# slaveMeteo.net
KiCad netlist of a schematic drawn in EAGLE
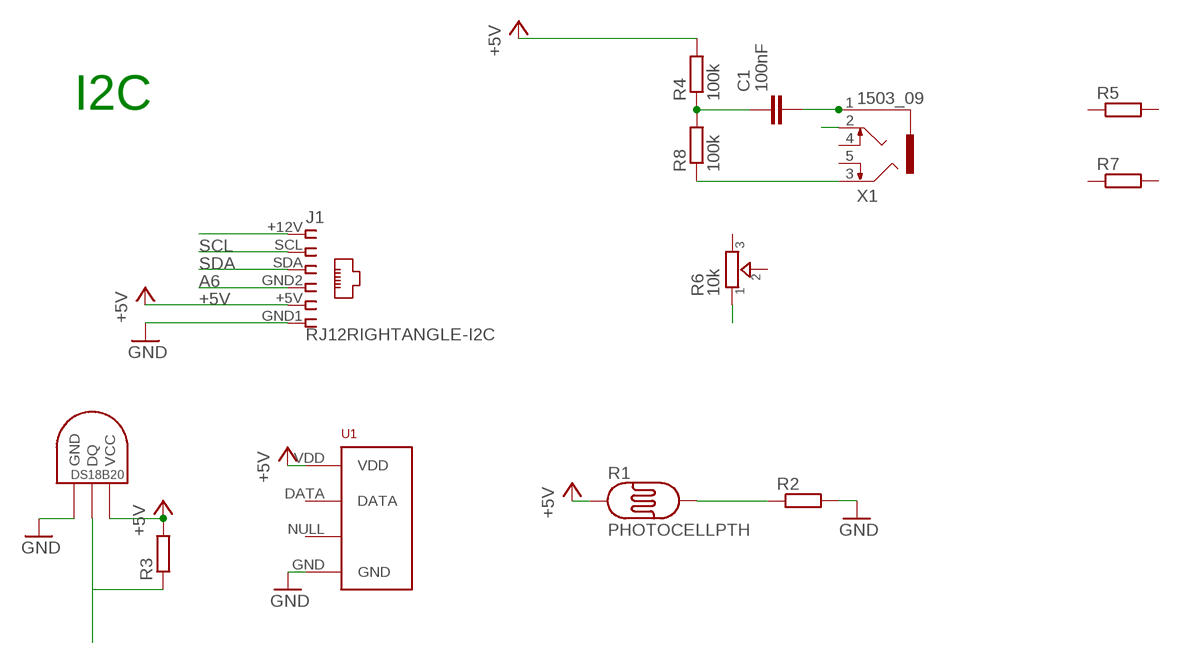
[diagram p0: schematic, sheet 1]
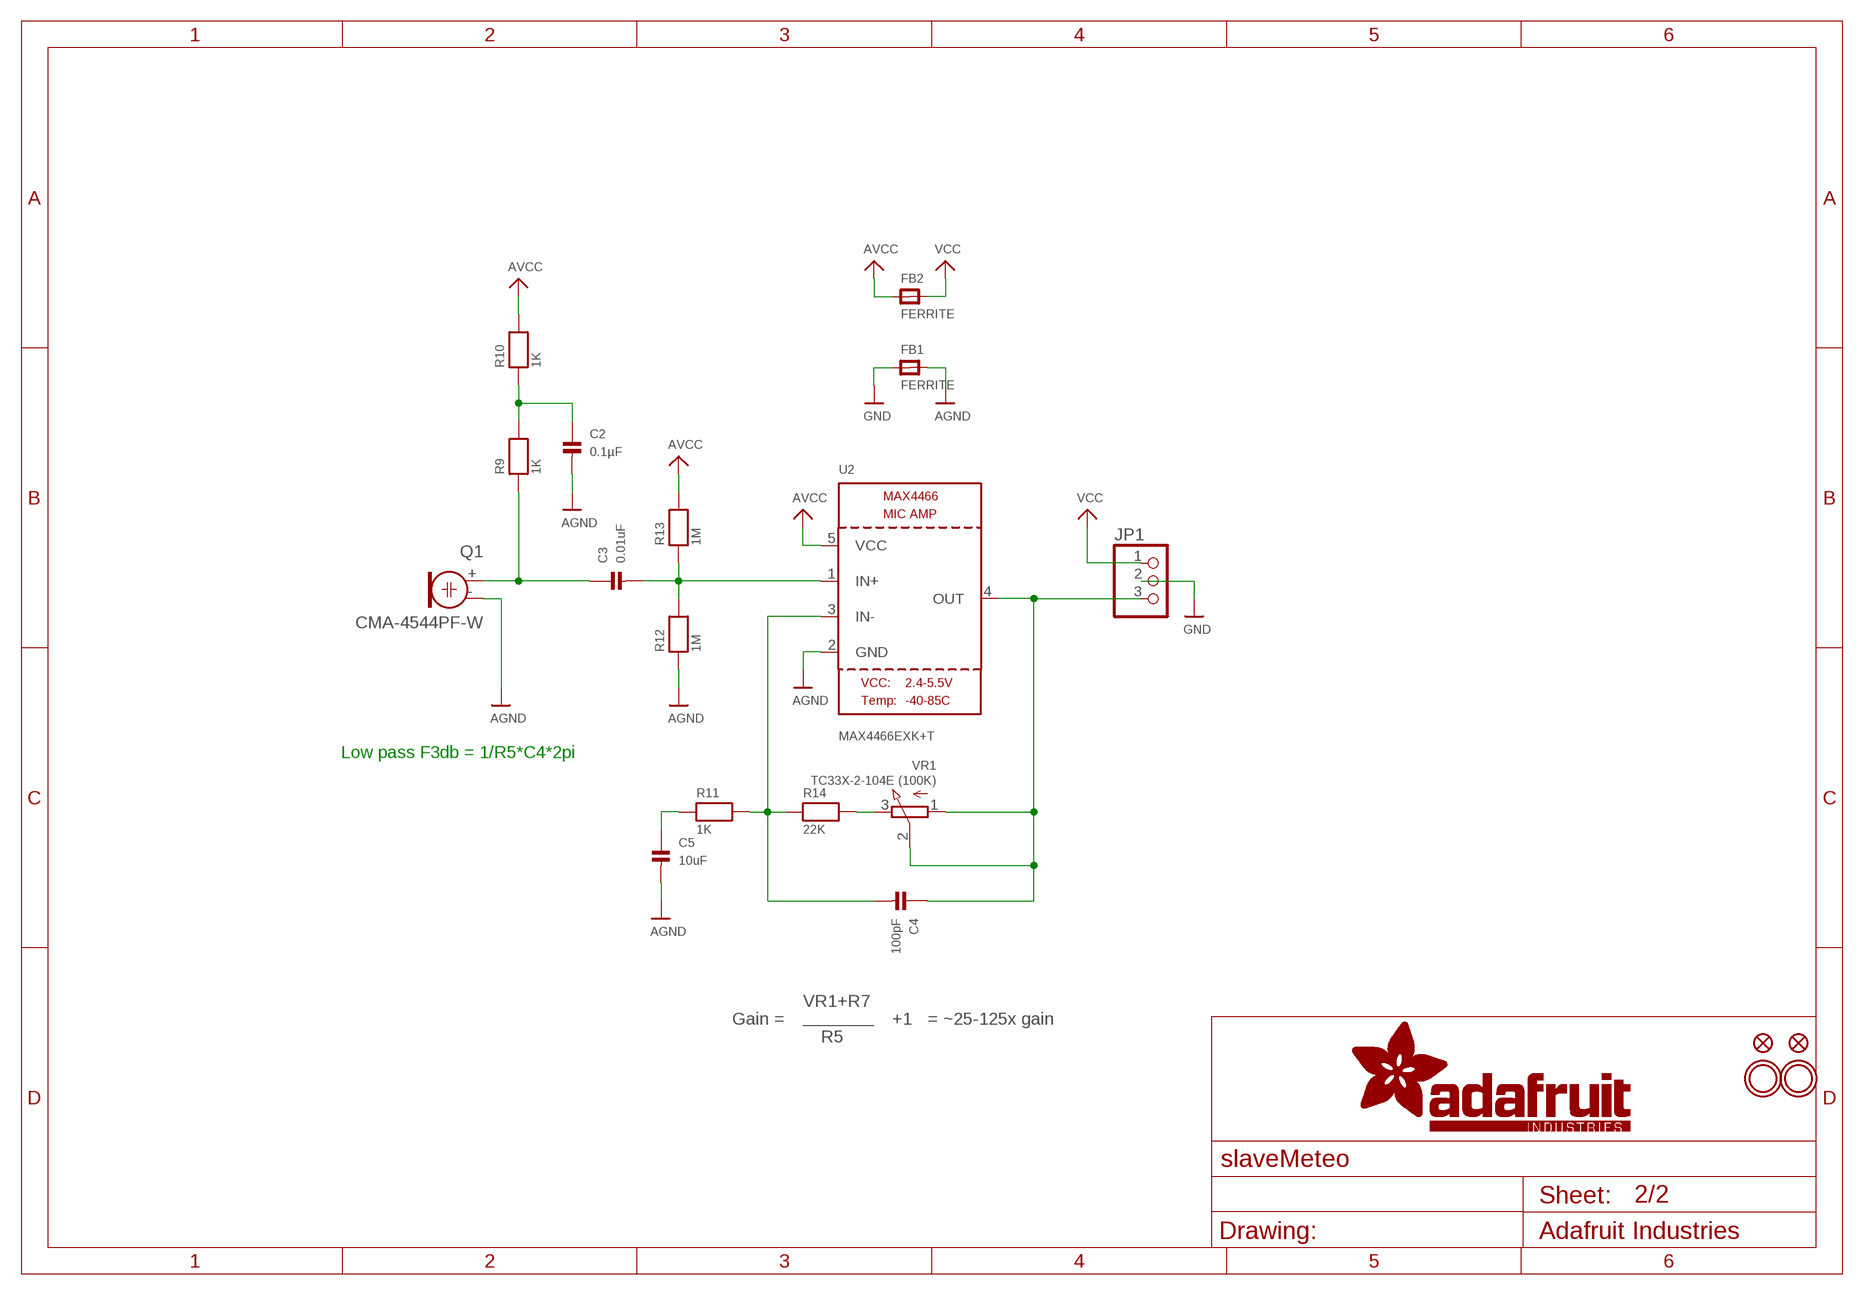
[diagram p1: schematic, sheet 2]

(export (version "E")
  (design (tool "Eeschema 10.0.6"))
  (components
    (comp (ref "C2")
      (value "0.1µF")
      (footprint "eagle-import:0805")
      (libsource (lib "eagle-import") (part "CAP_CERAMIC0805"))
    )
    (comp (ref "C3")
      (value "0.01uF")
      (footprint "eagle-import:0805")
      (libsource (lib "eagle-import") (part "CAP_CERAMIC0805"))
    )
    (comp (ref "C4")
      (value "100pF")
      (footprint "eagle-import:0805")
      (libsource (lib "eagle-import") (part "CAP_CERAMIC0805"))
    )
    (comp (ref "C5")
      (value "10uF")
      (footprint "eagle-import:0805")
      (libsource (lib "eagle-import") (part "CAP_CERAMIC0805"))
    )
    (comp (ref "FB1")
      (value "FERRITE")
      (footprint "eagle-import:0805")
      (libsource (lib "eagle-import") (part "FERRITE0805"))
    )
    (comp (ref "FB2")
      (value "FERRITE")
      (footprint "eagle-import:0805")
      (libsource (lib "eagle-import") (part "FERRITE0805"))
    )
    (comp (ref "FID1")
      (value "FIDUCIAL\"\"")
      (footprint "eagle-import:FIDUCIAL_1MM")
      (libsource (lib "eagle-import") (part "FIDUCIAL{dblquote}{dblquote}"))
    )
    (comp (ref "FID2")
      (value "FIDUCIAL\"\"")
      (footprint "eagle-import:FIDUCIAL_1MM")
      (libsource (lib "eagle-import") (part "FIDUCIAL{dblquote}{dblquote}"))
    )
    (comp (ref "JP1")
      (value "HEADER-1X376MIL")
      (footprint "eagle-import:1X03_ROUND_76")
      (libsource (lib "eagle-import") (part "HEADER-1X376MIL"))
    )
    (comp (ref "Q1")
      (value "CMA-4544PF-W")
      (footprint "eagle-import:ELECTRET_9.7")
      (libsource (lib "eagle-import") (part "ELECTRET"))
    )
    (comp (ref "R9")
      (value "1K")
      (footprint "eagle-import:0805")
      (libsource (lib "eagle-import") (part "RESISTOR0805"))
    )
    (comp (ref "R10")
      (value "1K")
      (footprint "eagle-import:0805")
      (libsource (lib "eagle-import") (part "RESISTOR0805"))
    )
    (comp (ref "R11")
      (value "1K")
      (footprint "eagle-import:0805")
      (libsource (lib "eagle-import") (part "RESISTOR0805"))
    )
    (comp (ref "R12")
      (value "1M")
      (footprint "eagle-import:0805")
      (libsource (lib "eagle-import") (part "RESISTOR0805"))
    )
    (comp (ref "R13")
      (value "1M")
      (footprint "eagle-import:0805")
      (libsource (lib "eagle-import") (part "RESISTOR0805"))
    )
    (comp (ref "R14")
      (value "22K")
      (footprint "eagle-import:0805")
      (libsource (lib "eagle-import") (part "RESISTOR0805"))
    )
    (comp (ref "U$14")
      (value "MOUNTINGHOLE2.5")
      (footprint "eagle-import:MOUNTINGHOLE_2.5_PLATED")
      (libsource (lib "eagle-import") (part "MOUNTINGHOLE2.5"))
    )
    (comp (ref "U$15")
      (value "MOUNTINGHOLE2.5")
      (footprint "eagle-import:MOUNTINGHOLE_2.5_PLATED")
      (libsource (lib "eagle-import") (part "MOUNTINGHOLE2.5"))
    )
    (comp (ref "U2")
      (value "MAX4466EXK+T")
      (footprint "eagle-import:SC70-5")
      (libsource (lib "eagle-import") (part "MAX4466{dblquote}{dblquote}"))
    )
    (comp (ref "VR1")
      (value "TC33X-2-104E (100K)")
      (footprint "eagle-import:TRIMPOT_BOURNS_TC33X-2")
      (libsource (lib "eagle-import") (part "TRIMPOTTC33X-2"))
    )
    (comp (ref "C1")
      (value "100nF")
      (footprint "eagle-import:C805")
      (libsource (lib "eagle-import") (part "CAPACITOR_NPOL-0805"))
    )
    (comp (ref "J1")
      (value "RJ12RIGHTANGLE-I2C")
      (footprint "eagle-import:RJ12-RIGHTANGLE-I2C")
      (libsource (lib "eagle-import") (part "RJ12RIGHTANGLE-I2C"))
    )
    (comp (ref "R1")
      (value "PHOTOCELLPTH")
      (footprint "eagle-import:PHOTOCELL")
      (libsource (lib "eagle-import") (part "PHOTOCELLPTH"))
    )
    (comp (ref "R2")
      (value "R-EU_R0805")
      (footprint "eagle-import:R0805")
      (libsource (lib "eagle-import") (part "R-EU_R0805"))
    )
    (comp (ref "R3")
      (value "R-EU_R0805")
      (footprint "eagle-import:R0805")
      (libsource (lib "eagle-import") (part "R-EU_R0805"))
    )
    (comp (ref "R4")
      (value "100k")
      (footprint "eagle-import:R0805")
      (libsource (lib "eagle-import") (part "R-EU_R0805"))
    )
    (comp (ref "R5")
      (value "R-EU_R0805")
      (footprint "eagle-import:R0805")
      (libsource (lib "eagle-import") (part "R-EU_R0805"))
    )
    (comp (ref "R6")
      (value "10k")
      (footprint "eagle-import:TRIMMER_3362P")
      (libsource (lib "eagle-import") (part "TRIMMER-3362P"))
    )
    (comp (ref "R7")
      (value "R-EU_R0805")
      (footprint "eagle-import:R0805")
      (libsource (lib "eagle-import") (part "R-EU_R0805"))
    )
    (comp (ref "R8")
      (value "100k")
      (footprint "eagle-import:R0805")
      (libsource (lib "eagle-import") (part "R-EU_R0805"))
    )
    (comp (ref "U$1")
      (value "DS1820TO92")
      (footprint "eagle-import:DS1820")
      (libsource (lib "eagle-import") (part "DS1820TO92"))
    )
    (comp (ref "U1")
      (value "RHT03_DHT-22_AM2302RA")
      (footprint "eagle-import:RHT03_DHT-22_RA")
      (libsource (lib "eagle-import") (part "RHT03_DHT-22_AM2302RA"))
    )
    (comp (ref "X1")
      (value "1503_09")
      (footprint "eagle-import:1503_09")
      (libsource (lib "eagle-import") (part "1503_09"))
    )
  )
  (nets
    (net (code "1") (name "+5V") (class "Default")
      (node (ref "J1") (pin "+5V") (pinfunction "5_+5V") (pintype "bidirectional"))
      (node (ref "R1") (pin "1") (pinfunction "P$1_1") (pintype "bidirectional"))
      (node (ref "R3") (pin "2") (pinfunction "2_2") (pintype "passive"))
      (node (ref "R4") (pin "2") (pinfunction "2_2") (pintype "passive"))
      (node (ref "U$1") (pin "VDD") (pinfunction "VCC_VDD") (pintype "power_in"))
      (node (ref "U1") (pin "VDD") (pinfunction "VDD_VDD") (pintype "power_in"))
    )
    (net (code "2") (name "A6") (class "Default")
      (node (ref "J1") (pin "GND2") (pinfunction "4_GND2") (pintype "bidirectional"))
    )
    (net (code "3") (name "AGND") (class "Default")
      (node (ref "C2") (pin "2") (pinfunction "P$2_2") (pintype "passive"))
      (node (ref "C5") (pin "2") (pinfunction "P$2_2") (pintype "passive"))
      (node (ref "FB1") (pin "2") (pinfunction "P$2_2") (pintype "passive"))
      (node (ref "Q1") (pin "-") (pinfunction "1_-") (pintype "passive"))
      (node (ref "R12") (pin "1") (pinfunction "1_1") (pintype "passive"))
      (node (ref "U2") (pin "2") (pinfunction "GND_2") (pintype "bidirectional"))
    )
    (net (code "4") (name "AVCC") (class "Default")
      (node (ref "FB2") (pin "1") (pinfunction "P$1_1") (pintype "passive"))
      (node (ref "R10") (pin "2") (pinfunction "2_2") (pintype "passive"))
      (node (ref "R13") (pin "2") (pinfunction "2_2") (pintype "passive"))
      (node (ref "U2") (pin "5") (pinfunction "VCC_5") (pintype "bidirectional"))
    )
    (net (code "5") (name "GND") (class "Default")
      (node (ref "FB1") (pin "1") (pinfunction "P$1_1") (pintype "passive"))
      (node (ref "J1") (pin "GND1") (pinfunction "6_GND1") (pintype "bidirectional"))
      (node (ref "JP1") (pin "2") (pinfunction "2_2") (pintype "passive"))
      (node (ref "R2") (pin "2") (pinfunction "2_2") (pintype "passive"))
      (node (ref "U$1") (pin "GND") (pinfunction "GND_GND") (pintype "power_in"))
      (node (ref "U1") (pin "GND") (pinfunction "GND_GND") (pintype "power_in"))
    )
    (net (code "6") (name "Net-(C1-Pad1)") (class "Default")
      (node (ref "C1") (pin "1") (pinfunction "1_1") (pintype "passive"))
      (node (ref "R4") (pin "1") (pinfunction "1_1") (pintype "passive"))
      (node (ref "R8") (pin "2") (pinfunction "2_2") (pintype "passive"))
    )
    (net (code "7") (name "Net-(C1-Pad2)") (class "Default")
      (node (ref "C1") (pin "2") (pinfunction "2_2") (pintype "passive"))
      (node (ref "X1") (pin "1") (pinfunction "1_1") (pintype "passive"))
    )
    (net (code "8") (name "Net-(C2-P$1)") (class "Default")
      (node (ref "C2") (pin "1") (pinfunction "P$1_1") (pintype "passive"))
      (node (ref "R10") (pin "1") (pinfunction "1_1") (pintype "passive"))
      (node (ref "R9") (pin "2") (pinfunction "2_2") (pintype "passive"))
    )
    (net (code "9") (name "Net-(C3-P$1)") (class "Default")
      (node (ref "C3") (pin "1") (pinfunction "P$1_1") (pintype "passive"))
      (node (ref "Q1") (pin "+") (pinfunction "2_+") (pintype "passive"))
      (node (ref "R9") (pin "1") (pinfunction "1_1") (pintype "passive"))
    )
    (net (code "10") (name "Net-(C3-P$2)") (class "Default")
      (node (ref "C3") (pin "2") (pinfunction "P$2_2") (pintype "passive"))
      (node (ref "R12") (pin "2") (pinfunction "2_2") (pintype "passive"))
      (node (ref "R13") (pin "1") (pinfunction "1_1") (pintype "passive"))
      (node (ref "U2") (pin "1") (pinfunction "IN+_1") (pintype "bidirectional"))
    )
    (net (code "11") (name "Net-(C4-P$1)") (class "Default")
      (node (ref "C4") (pin "1") (pinfunction "P$1_1") (pintype "passive"))
      (node (ref "JP1") (pin "3") (pinfunction "3_3") (pintype "passive"))
      (node (ref "U2") (pin "4") (pinfunction "OUT_4") (pintype "bidirectional"))
      (node (ref "VR1") (pin "1") (pinfunction "A_1") (pintype "passive"))
      (node (ref "VR1") (pin "2") (pinfunction "S_2") (pintype "passive"))
    )
    (net (code "12") (name "Net-(C4-P$2)") (class "Default")
      (node (ref "C4") (pin "2") (pinfunction "P$2_2") (pintype "passive"))
      (node (ref "R11") (pin "2") (pinfunction "2_2") (pintype "passive"))
      (node (ref "R14") (pin "1") (pinfunction "1_1") (pintype "passive"))
      (node (ref "U2") (pin "3") (pinfunction "IN-_3") (pintype "bidirectional"))
    )
    (net (code "13") (name "Net-(C5-P$1)") (class "Default")
      (node (ref "C5") (pin "1") (pinfunction "P$1_1") (pintype "passive"))
      (node (ref "R11") (pin "1") (pinfunction "1_1") (pintype "passive"))
    )
    (net (code "14") (name "Net-(R1-P$2)") (class "Default")
      (node (ref "R1") (pin "2") (pinfunction "P$2_2") (pintype "bidirectional"))
      (node (ref "R2") (pin "1") (pinfunction "1_1") (pintype "passive"))
    )
    (net (code "15") (name "Net-(R3-Pad1)") (class "Default")
      (node (ref "R3") (pin "1") (pinfunction "1_1") (pintype "passive"))
      (node (ref "U$1") (pin "DQ") (pinfunction "DQ_DQ") (pintype "bidirectional"))
    )
    (net (code "16") (name "Net-(R8-Pad1)") (class "Default")
      (node (ref "R8") (pin "1") (pinfunction "1_1") (pintype "passive"))
      (node (ref "X1") (pin "3") (pinfunction "3_3") (pintype "passive"))
    )
    (net (code "17") (name "Net-(VR1-E)") (class "Default")
      (node (ref "R14") (pin "2") (pinfunction "2_2") (pintype "passive"))
      (node (ref "VR1") (pin "3") (pinfunction "E_3") (pintype "passive"))
    )
    (net (code "18") (name "SCL") (class "Default")
      (node (ref "J1") (pin "SCL") (pinfunction "2_SCL") (pintype "bidirectional"))
    )
    (net (code "19") (name "SDA") (class "Default")
      (node (ref "J1") (pin "SDA") (pinfunction "3_SDA") (pintype "bidirectional"))
    )
    (net (code "20") (name "VCC") (class "Default")
      (node (ref "FB2") (pin "2") (pinfunction "P$2_2") (pintype "passive"))
      (node (ref "JP1") (pin "1") (pinfunction "1_1") (pintype "passive"))
    )
    (net (code "21") (name "unconnected-(J1-1-Pad+12V)") (class "Default")
      (node (ref "J1") (pin "+12V") (pinfunction "1_+12V") (pintype "bidirectional"))
    )
    (net (code "22") (name "unconnected-(R5-Pad1)") (class "Default")
      (node (ref "R5") (pin "1") (pinfunction "1_1") (pintype "passive"))
    )
    (net (code "23") (name "unconnected-(R5-Pad2)") (class "Default")
      (node (ref "R5") (pin "2") (pinfunction "2_2") (pintype "passive"))
    )
    (net (code "24") (name "unconnected-(R6-Pad1)") (class "Default")
      (node (ref "R6") (pin "1") (pinfunction "1_1") (pintype "passive"))
    )
    (net (code "25") (name "unconnected-(R6-Pad2)") (class "Default")
      (node (ref "R6") (pin "2") (pinfunction "2_2") (pintype "passive"))
    )
    (net (code "26") (name "unconnected-(R6-Pad3)") (class "Default")
      (node (ref "R6") (pin "3") (pinfunction "3_3") (pintype "passive"))
    )
    (net (code "27") (name "unconnected-(R7-Pad1)") (class "Default")
      (node (ref "R7") (pin "1") (pinfunction "1_1") (pintype "passive"))
    )
    (net (code "28") (name "unconnected-(R7-Pad2)") (class "Default")
      (node (ref "R7") (pin "2") (pinfunction "2_2") (pintype "passive"))
    )
    (net (code "29") (name "unconnected-(U1-PadDATA)") (class "Default")
      (node (ref "U1") (pin "DATA") (pinfunction "DATA_DATA") (pintype "bidirectional"))
    )
    (net (code "30") (name "unconnected-(U1-PadNULL)") (class "Default")
      (node (ref "U1") (pin "NULL") (pinfunction "NULL_NULL") (pintype "no_connect"))
    )
    (net (code "31") (name "unconnected-(X1-Pad2)") (class "Default")
      (node (ref "X1") (pin "2") (pinfunction "2_2") (pintype "passive"))
    )
    (net (code "32") (name "unconnected-(X1-Pad4)") (class "Default")
      (node (ref "X1") (pin "4") (pinfunction "4_4") (pintype "passive"))
    )
    (net (code "33") (name "unconnected-(X1-Pad5)") (class "Default")
      (node (ref "X1") (pin "5") (pinfunction "5_5") (pintype "passive"))
    )
  )
)
